# 02_MCU.net
KiCad netlist of a schematic drawn in Altium Designer
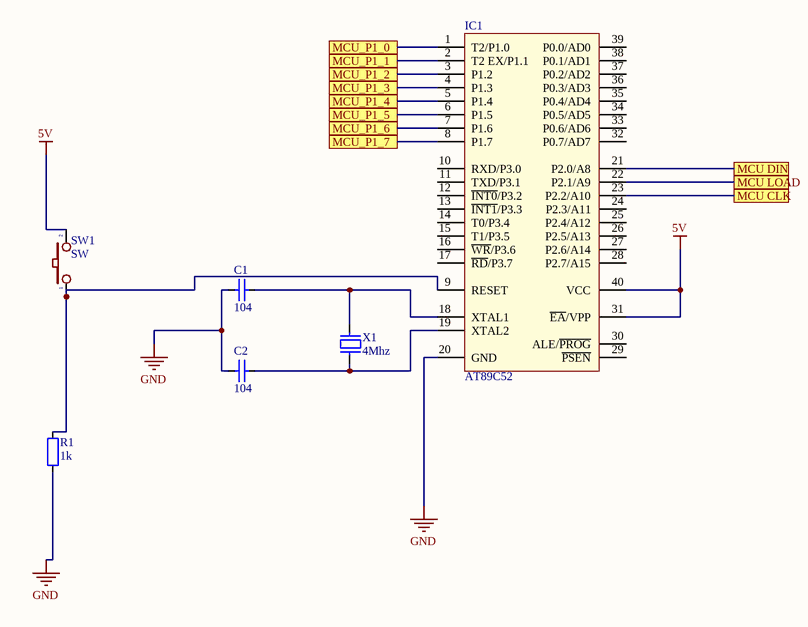
[diagram p0: [02] MCU.SchDoc]

(export (version "E")
  (design (tool "Eeschema 10.0.6"))
  (components
    (comp (ref "C1")
      (value "104")
      (footprint "CAP_0805")
      (description "Capacitor")
      (fields (field (name "PUBLISHER") "Altium Limited"))
      (libsource (lib "My Library") (part "CapSMD"))
    )
    (comp (ref "C2")
      (value "104")
      (footprint "CAP_0805")
      (description "Capacitor")
      (fields (field (name "PUBLISHER") "Altium Limited"))
      (libsource (lib "My Library") (part "CapSMD"))
    )
    (comp (ref "IC1")
      (value "AT89C52")
      (footprint "DIP40/W0.6")
      (description "Atmel AT89C52, 8k Byte Flash Memory , 40 Pin")
      (libsource (lib "My Library") (part "AT89C52"))
    )
    (comp (ref "R1")
      (value "1k")
      (footprint "RES-SMD-0805")
      (description "Resistor")
      (fields
        (field (name "MANUFACTURER") "Generic Components")
        (field (name "PUBLISHER") "Altium Hobart Technology Centre")
      )
      (libsource (lib "My Library") (part "Resistor - SMD"))
    )
    (comp (ref "SW1")
      (value "SW")
      (footprint "SW2")
      (description "Switch button 2 pin")
      (libsource (lib "My Library") (part "SW2"))
    )
    (comp (ref "X1")
      (value "4Mhz")
      (footprint "XT2")
      (description "Crystal For all Crystal 2pin.")
      (libsource (lib "My Library") (part "XT2"))
    )
  )
  (nets
    (net (code "1") (name "/MCU CLK") (class "Default")
      (node (ref "IC1") (pin "23") (pinfunction "P2.2/A10_23") (pintype "passive"))
    )
    (net (code "2") (name "/MCU DIN") (class "Default")
      (node (ref "IC1") (pin "21") (pinfunction "P2.0/A8_21") (pintype "passive"))
    )
    (net (code "3") (name "/MCU LOAD") (class "Default")
      (node (ref "IC1") (pin "22") (pinfunction "P2.1/A9_22") (pintype "passive"))
    )
    (net (code "4") (name "/MCU_P1_0") (class "Default")
      (node (ref "IC1") (pin "1") (pinfunction "T2/P1.0_1") (pintype "passive"))
    )
    (net (code "5") (name "/MCU_P1_1") (class "Default")
      (node (ref "IC1") (pin "2") (pinfunction "T2_EX/P1.1_2") (pintype "passive"))
    )
    (net (code "6") (name "/MCU_P1_2") (class "Default")
      (node (ref "IC1") (pin "3") (pinfunction "P1.2_3") (pintype "passive"))
    )
    (net (code "7") (name "/MCU_P1_3") (class "Default")
      (node (ref "IC1") (pin "4") (pinfunction "P1.3_4") (pintype "passive"))
    )
    (net (code "8") (name "/MCU_P1_4") (class "Default")
      (node (ref "IC1") (pin "5") (pinfunction "P1.4_5") (pintype "passive"))
    )
    (net (code "9") (name "/MCU_P1_5") (class "Default")
      (node (ref "IC1") (pin "6") (pinfunction "P1.5_6") (pintype "passive"))
    )
    (net (code "10") (name "/MCU_P1_6") (class "Default")
      (node (ref "IC1") (pin "7") (pinfunction "P1.6_7") (pintype "passive"))
    )
    (net (code "11") (name "/MCU_P1_7") (class "Default")
      (node (ref "IC1") (pin "8") (pinfunction "P1.7_8") (pintype "passive"))
    )
    (net (code "12") (name "5V") (class "Default")
      (node (ref "IC1") (pin "31") (pinfunction "~{EA}/VPP_31") (pintype "passive"))
      (node (ref "IC1") (pin "40") (pinfunction "VCC_40") (pintype "power_in"))
      (node (ref "SW1") (pin "2") (pinfunction "2_2") (pintype "passive"))
    )
    (net (code "13") (name "GND") (class "Default")
      (node (ref "C1") (pin "1") (pinfunction "1_1") (pintype "passive"))
      (node (ref "C2") (pin "1") (pinfunction "1_1") (pintype "passive"))
      (node (ref "IC1") (pin "20") (pinfunction "GND_20") (pintype "open_emitter"))
      (node (ref "R1") (pin "1") (pinfunction "1_1") (pintype "passive"))
    )
    (net (code "14") (name "Net-(IC1-RESET)") (class "Default")
      (node (ref "IC1") (pin "9") (pinfunction "RESET_9") (pintype "passive"))
      (node (ref "R1") (pin "2") (pinfunction "2_2") (pintype "passive"))
      (node (ref "SW1") (pin "1") (pinfunction "1_1") (pintype "passive"))
    )
    (net (code "15") (name "Net-(IC1-XTAL1)") (class "Default")
      (node (ref "C1") (pin "2") (pinfunction "2_2") (pintype "passive"))
      (node (ref "IC1") (pin "18") (pinfunction "XTAL1_18") (pintype "passive"))
      (node (ref "X1") (pin "2") (pinfunction "2_2") (pintype "passive"))
    )
    (net (code "16") (name "Net-(IC1-XTAL2)") (class "Default")
      (node (ref "C2") (pin "2") (pinfunction "2_2") (pintype "passive"))
      (node (ref "IC1") (pin "19") (pinfunction "XTAL2_19") (pintype "passive"))
      (node (ref "X1") (pin "1") (pinfunction "1_1") (pintype "passive"))
    )
    (net (code "17") (name "unconnected-(IC1-ALE{slash}~{PROG}-Pad30)") (class "Default")
      (node (ref "IC1") (pin "30") (pinfunction "ALE/~{PROG}_30") (pintype "passive"))
    )
    (net (code "18") (name "unconnected-(IC1-P0.0{slash}AD0-Pad39)") (class "Default")
      (node (ref "IC1") (pin "39") (pinfunction "P0.0/AD0_39") (pintype "passive"))
    )
    (net (code "19") (name "unconnected-(IC1-P0.1{slash}AD1-Pad38)") (class "Default")
      (node (ref "IC1") (pin "38") (pinfunction "P0.1/AD1_38") (pintype "passive"))
    )
    (net (code "20") (name "unconnected-(IC1-P0.2{slash}AD2-Pad37)") (class "Default")
      (node (ref "IC1") (pin "37") (pinfunction "P0.2/AD2_37") (pintype "passive"))
    )
    (net (code "21") (name "unconnected-(IC1-P0.3{slash}AD3-Pad36)") (class "Default")
      (node (ref "IC1") (pin "36") (pinfunction "P0.3/AD3_36") (pintype "passive"))
    )
    (net (code "22") (name "unconnected-(IC1-P0.4{slash}AD4-Pad35)") (class "Default")
      (node (ref "IC1") (pin "35") (pinfunction "P0.4/AD4_35") (pintype "passive"))
    )
    (net (code "23") (name "unconnected-(IC1-P0.5{slash}AD5-Pad34)") (class "Default")
      (node (ref "IC1") (pin "34") (pinfunction "P0.5/AD5_34") (pintype "passive"))
    )
    (net (code "24") (name "unconnected-(IC1-P0.6{slash}AD6-Pad33)") (class "Default")
      (node (ref "IC1") (pin "33") (pinfunction "P0.6/AD6_33") (pintype "passive"))
    )
    (net (code "25") (name "unconnected-(IC1-P0.7{slash}AD7-Pad32)") (class "Default")
      (node (ref "IC1") (pin "32") (pinfunction "P0.7/AD7_32") (pintype "passive"))
    )
    (net (code "26") (name "unconnected-(IC1-P2.3{slash}A11-Pad24)") (class "Default")
      (node (ref "IC1") (pin "24") (pinfunction "P2.3/A11_24") (pintype "passive"))
    )
    (net (code "27") (name "unconnected-(IC1-P2.4{slash}A12-Pad25)") (class "Default")
      (node (ref "IC1") (pin "25") (pinfunction "P2.4/A12_25") (pintype "passive"))
    )
    (net (code "28") (name "unconnected-(IC1-P2.5{slash}A13-Pad26)") (class "Default")
      (node (ref "IC1") (pin "26") (pinfunction "P2.5/A13_26") (pintype "passive"))
    )
    (net (code "29") (name "unconnected-(IC1-P2.6{slash}A14-Pad27)") (class "Default")
      (node (ref "IC1") (pin "27") (pinfunction "P2.6/A14_27") (pintype "passive"))
    )
    (net (code "30") (name "unconnected-(IC1-P2.7{slash}A15-Pad28)") (class "Default")
      (node (ref "IC1") (pin "28") (pinfunction "P2.7/A15_28") (pintype "passive"))
    )
    (net (code "31") (name "unconnected-(IC1-RXD{slash}P3.0-Pad10)") (class "Default")
      (node (ref "IC1") (pin "10") (pinfunction "RXD/P3.0_10") (pintype "passive"))
    )
    (net (code "32") (name "unconnected-(IC1-T0{slash}P3.4-Pad14)") (class "Default")
      (node (ref "IC1") (pin "14") (pinfunction "T0/P3.4_14") (pintype "passive"))
    )
    (net (code "33") (name "unconnected-(IC1-T1{slash}P3.5-Pad15)") (class "Default")
      (node (ref "IC1") (pin "15") (pinfunction "T1/P3.5_15") (pintype "passive"))
    )
    (net (code "34") (name "unconnected-(IC1-TXD{slash}P3.1-Pad11)") (class "Default")
      (node (ref "IC1") (pin "11") (pinfunction "TXD/P3.1_11") (pintype "passive"))
    )
    (net (code "35") (name "unconnected-(IC1-~{INT0}{slash}P3.2-Pad12)") (class "Default")
      (node (ref "IC1") (pin "12") (pinfunction "~{INT0}/P3.2_12") (pintype "passive"))
    )
    (net (code "36") (name "unconnected-(IC1-~{INT1}{slash}P3.3-Pad13)") (class "Default")
      (node (ref "IC1") (pin "13") (pinfunction "~{INT1}/P3.3_13") (pintype "passive"))
    )
    (net (code "37") (name "unconnected-(IC1-~{PSEN}-Pad29)") (class "Default")
      (node (ref "IC1") (pin "29") (pinfunction "~{PSEN}_29") (pintype "passive"))
    )
    (net (code "38") (name "unconnected-(IC1-~{RD}{slash}P3.7-Pad17)") (class "Default")
      (node (ref "IC1") (pin "17") (pinfunction "~{RD}/P3.7_17") (pintype "passive"))
    )
    (net (code "39") (name "unconnected-(IC1-~{WR}{slash}P3.6-Pad16)") (class "Default")
      (node (ref "IC1") (pin "16") (pinfunction "~{WR}/P3.6_16") (pintype "passive"))
    )
  )
)
